# oscillator_tuned.net
KiCad netlist of a schematic drawn in Altium Designer
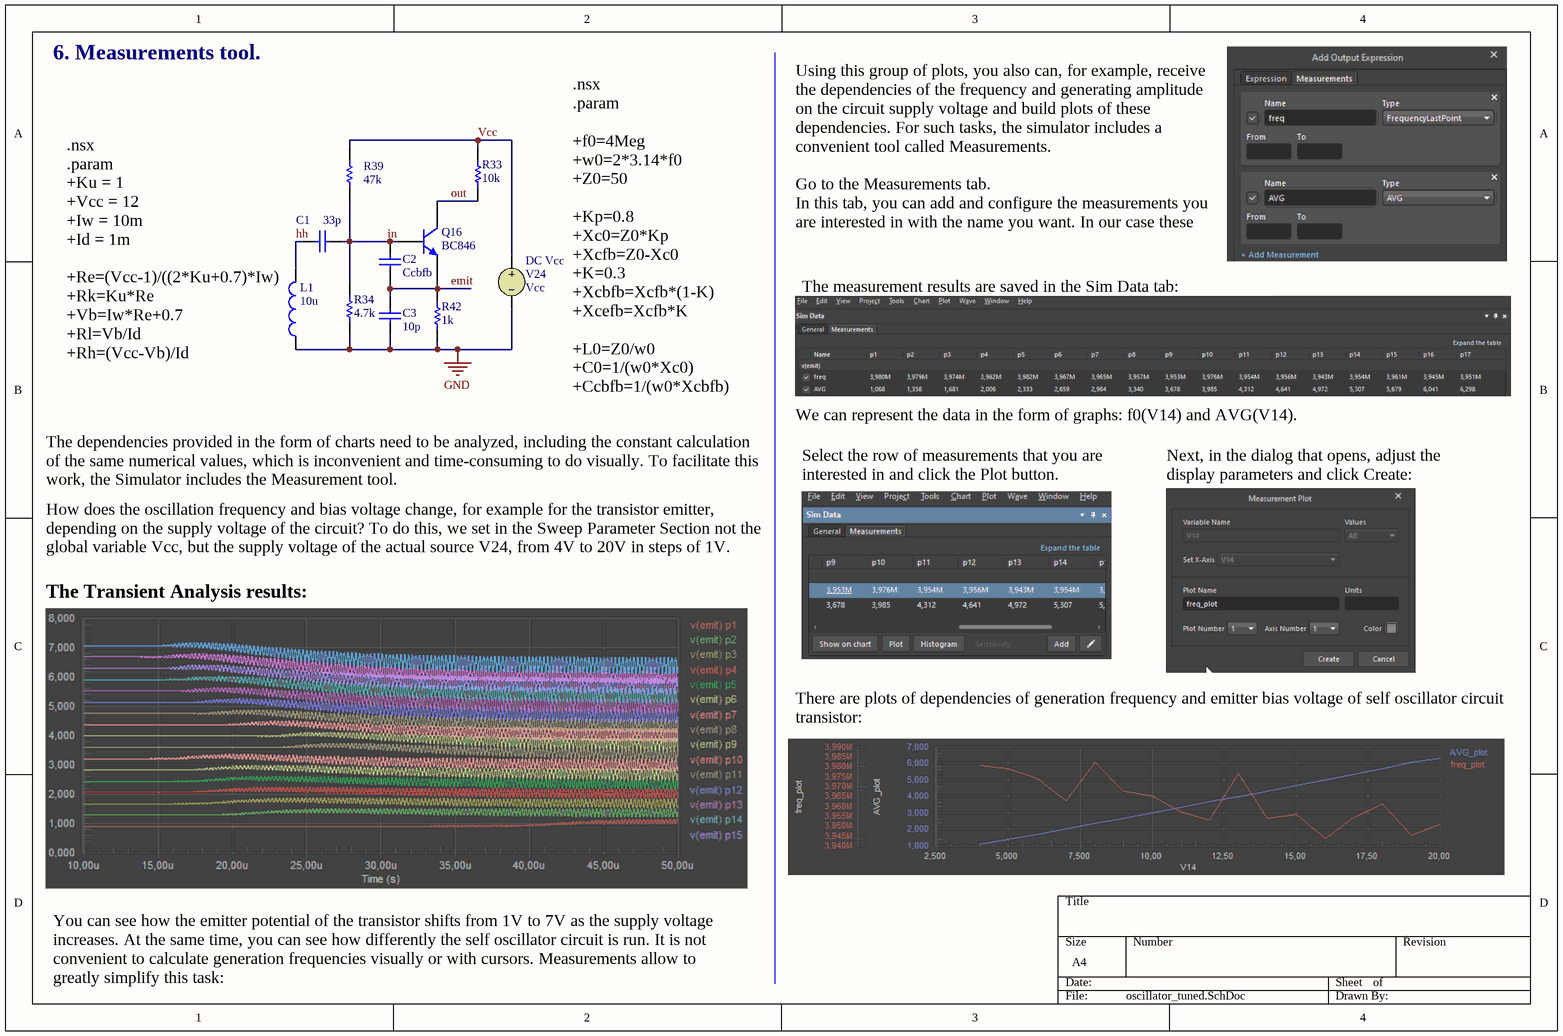
[diagram p0: oscillator_tuned.SchDoc]

(export (version "E")
  (design (tool "Eeschema 10.0.6"))
  (components
    (comp (ref "C1")
      (value "33p")
      (description "Capacitor")
      (libsource (lib "Simulation Generic Components") (part "Capacitor"))
    )
    (comp (ref "C2")
      (value "Ccbfb")
      (description "Capacitor")
      (libsource (lib "Simulation Generic Components") (part "Capacitor"))
    )
    (comp (ref "C3")
      (value "10p")
      (description "Capacitor")
      (libsource (lib "Simulation Generic Components") (part "Capacitor"))
    )
    (comp (ref "L1")
      (value "10u")
      (description "Inductor")
      (libsource (lib "Simulation Generic Components") (part "Inductor"))
    )
    (comp (ref "Q16")
      (value "BC846")
      (footprint "TO-92A")
      (description "NPN General Purpose Amplifier")
      (fields (field (name "PUBLISHER") "Altium Limited"))
      (libsource (lib "Miscellaneous Devices") (part "2N3904"))
    )
    (comp (ref "R33")
      (value "10k")
      (description "Resistor")
      (libsource (lib "Simulation Generic Components") (part "Resistor"))
    )
    (comp (ref "R34")
      (value "4.7k")
      (description "Resistor")
      (libsource (lib "Simulation Generic Components") (part "Resistor"))
    )
    (comp (ref "R39")
      (value "47k")
      (description "Resistor")
      (libsource (lib "Simulation Generic Components") (part "Resistor"))
    )
    (comp (ref "R42")
      (value "1k")
      (description "Resistor")
      (libsource (lib "Simulation Generic Components") (part "Resistor"))
    )
    (comp (ref "V24")
      (value "DC Vcc")
      (description "Voltage Source")
      (fields (field (name "ALTIUM_VALUE") "Vcc") (field (name "PUBLISHER") "Altium Limited"))
      (libsource (lib "Simulation Generic Components") (part "VSRC"))
    )
  )
  (nets
    (net (code "1") (name "/Vcc") (class "Default")
      (node (ref "R33") (pin "2") (pinfunction "2_2") (pintype "passive"))
      (node (ref "R39") (pin "2") (pinfunction "2_2") (pintype "passive"))
      (node (ref "V24") (pin "1") (pinfunction "1_1") (pintype "passive"))
    )
    (net (code "2") (name "/emit") (class "Default")
      (node (ref "C2") (pin "1") (pinfunction "1_1") (pintype "passive"))
      (node (ref "C3") (pin "2") (pinfunction "2_2") (pintype "passive"))
      (node (ref "Q16") (pin "1") (pinfunction "E_1") (pintype "passive"))
      (node (ref "R42") (pin "2") (pinfunction "2_2") (pintype "passive"))
    )
    (net (code "3") (name "/hh") (class "Default")
      (node (ref "C1") (pin "1") (pinfunction "1_1") (pintype "passive"))
      (node (ref "L1") (pin "2") (pinfunction "2_2") (pintype "passive"))
    )
    (net (code "4") (name "/in") (class "Default")
      (node (ref "C1") (pin "2") (pinfunction "2_2") (pintype "passive"))
      (node (ref "C2") (pin "2") (pinfunction "2_2") (pintype "passive"))
      (node (ref "Q16") (pin "2") (pinfunction "B_2") (pintype "passive"))
      (node (ref "R34") (pin "1") (pinfunction "1_1") (pintype "passive"))
      (node (ref "R39") (pin "1") (pinfunction "1_1") (pintype "passive"))
    )
    (net (code "5") (name "/out") (class "Default")
      (node (ref "Q16") (pin "3") (pinfunction "C_3") (pintype "passive"))
      (node (ref "R33") (pin "1") (pinfunction "1_1") (pintype "passive"))
    )
    (net (code "6") (name "GND") (class "Default")
      (node (ref "C3") (pin "1") (pinfunction "1_1") (pintype "passive"))
      (node (ref "L1") (pin "1") (pinfunction "1_1") (pintype "passive"))
      (node (ref "R34") (pin "2") (pinfunction "2_2") (pintype "passive"))
      (node (ref "R42") (pin "1") (pinfunction "1_1") (pintype "passive"))
      (node (ref "V24") (pin "2") (pinfunction "2_2") (pintype "passive"))
    )
  )
)
